# EEG_Preprocessing.net
KiCad netlist of a schematic drawn in Altium Designer
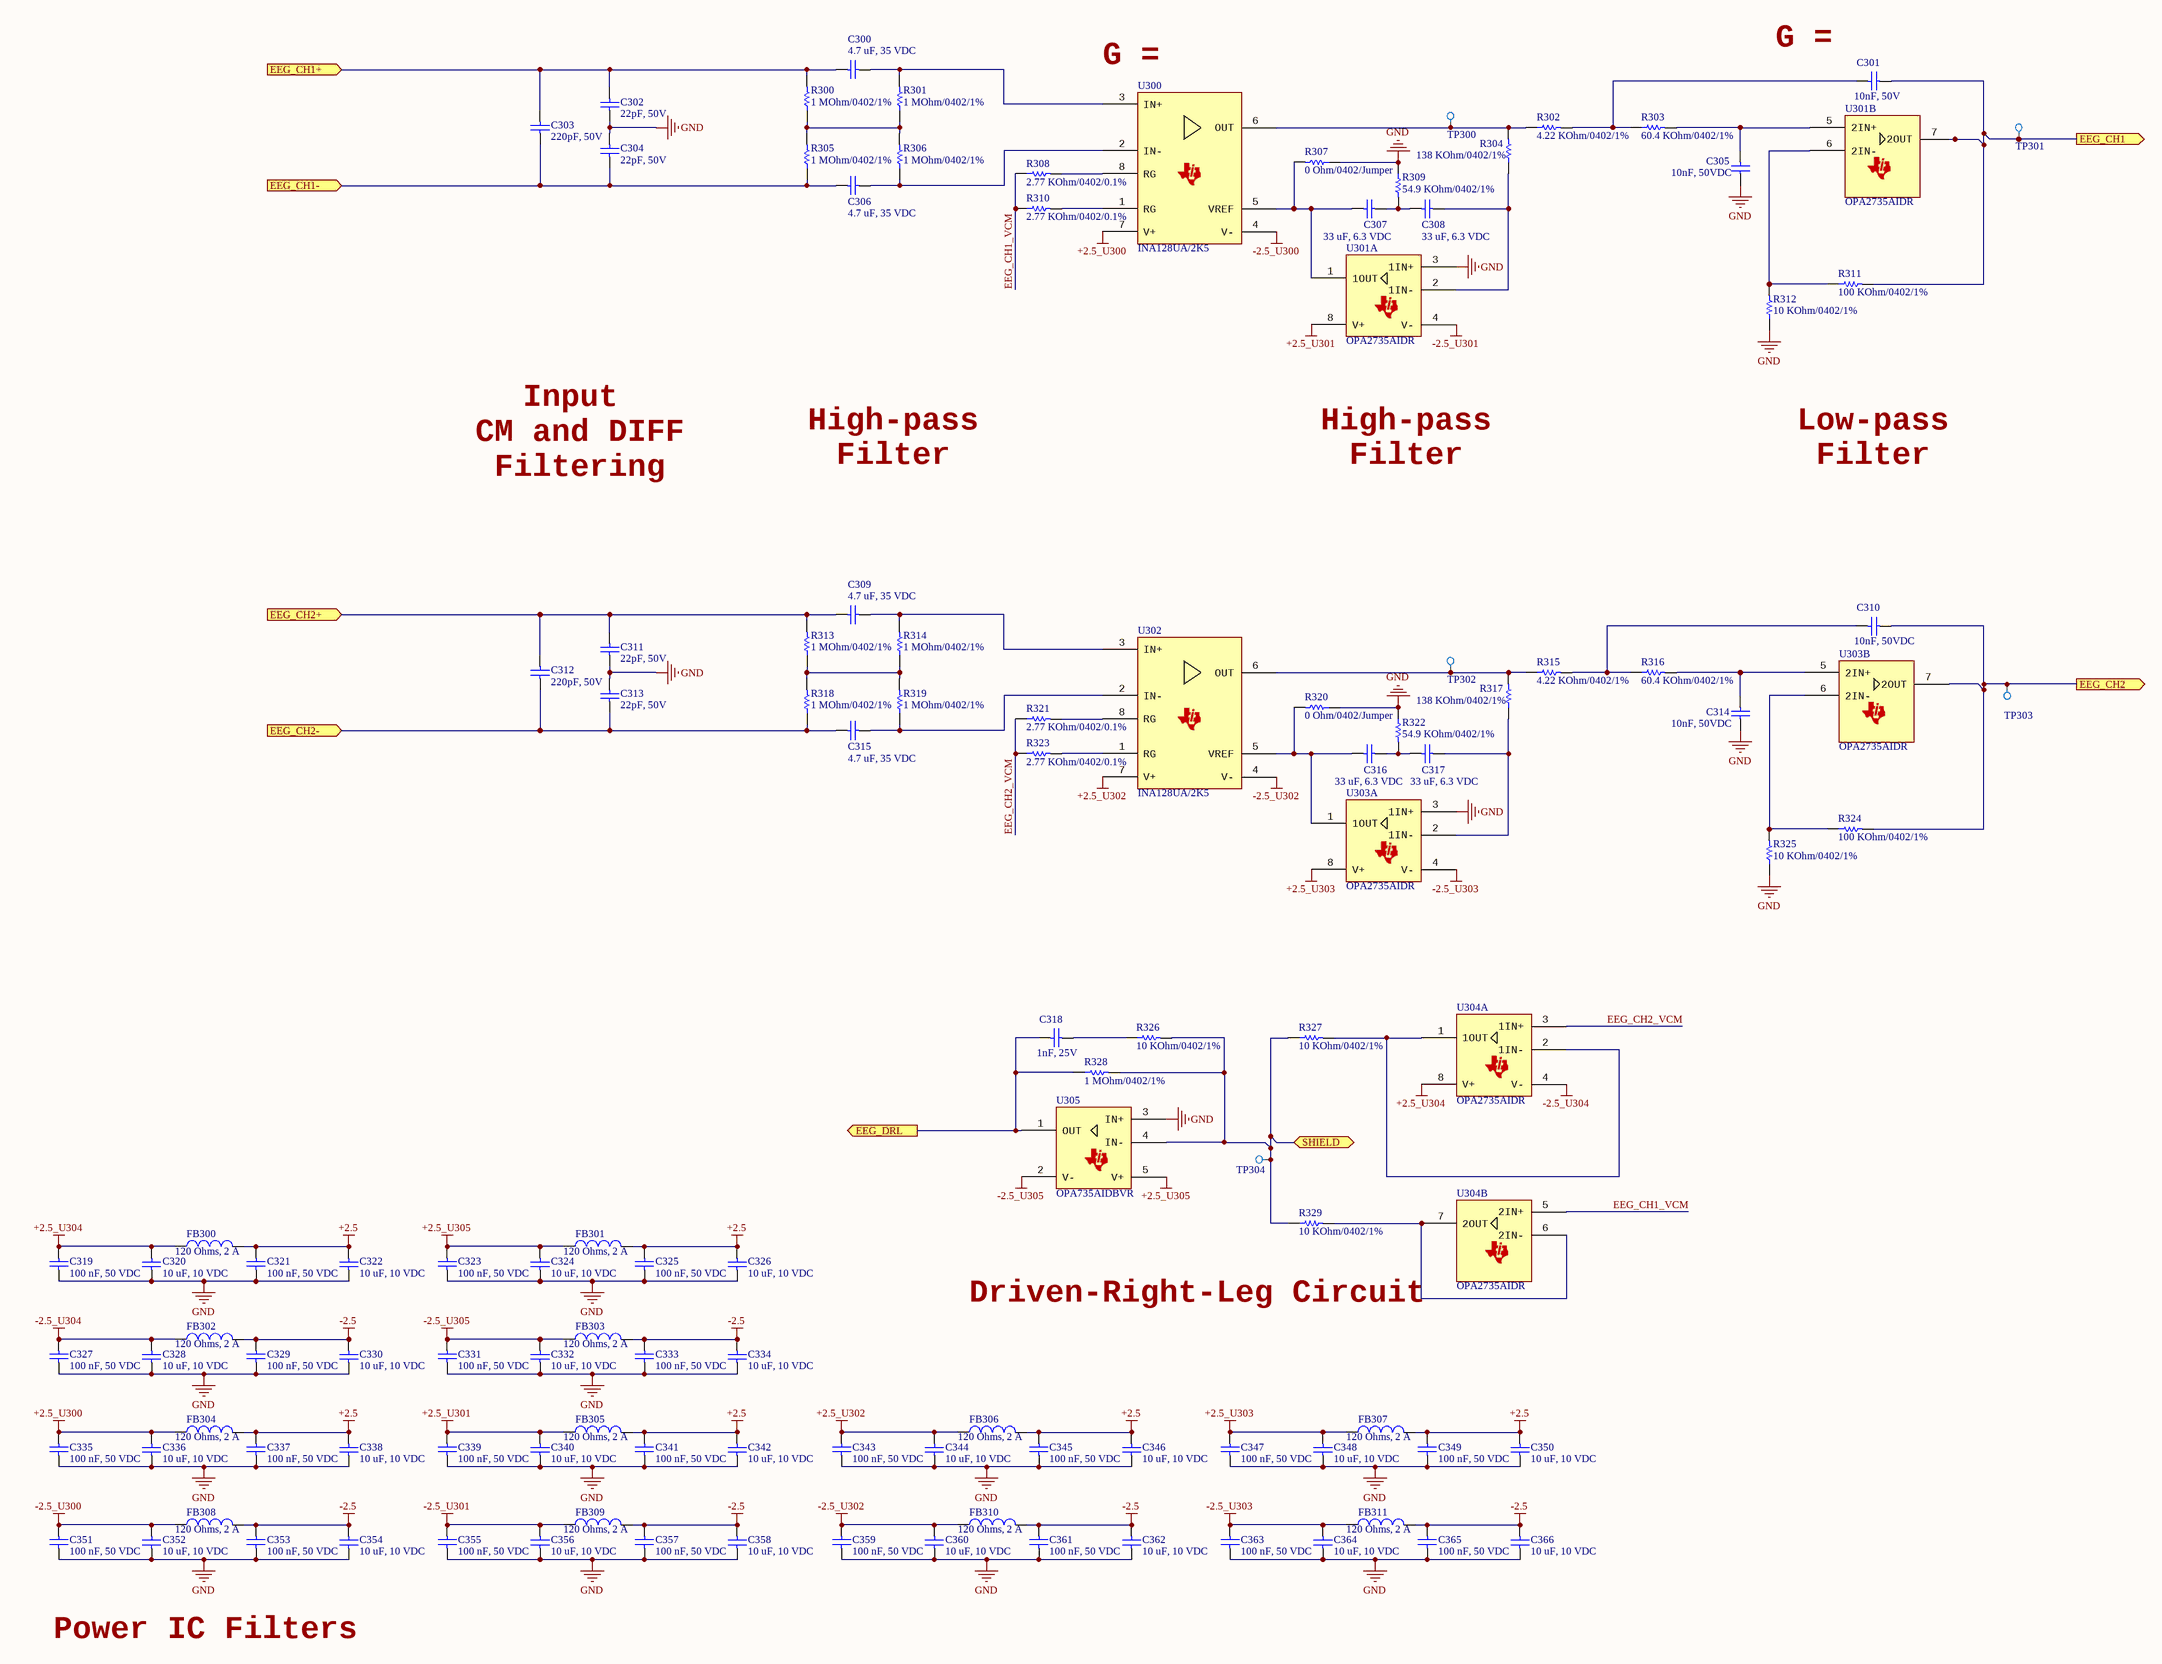
[diagram p0: EEG Preprocessing.SchDoc]

(export (version "E")
  (design (tool "Eeschema 10.0.6"))
  (components
    (comp (ref "C300")
      (value "4.7 uF, 35 VDC")
      (footprint "CAP_0603")
      (description "CAP, size 0603, 4.7 uF, 35 VDC")
      (fields (field (name "TOLERANCE") "+/-10%"))
      (libsource (lib "Altium_Ceramic_Cap") (part "0106034751035"))
    )
    (comp (ref "C301")
      (value "10nF, 50V")
      (footprint "WCAP-CSGP_0402_L1W0.5H0.5")
      (description "WCAP-CSGP Multilayer Ceramic Chip Capacitor, General Purpose, size 0402, X7R, 10nF, 50V")
      (fields
        (field (name "MANUFACTURER PART NUMBER") "885012205067")
        (field (name "MANUFACTURER") "Wurth Elektronik")
      )
      (libsource (lib "Altium_WCAP-CSGP (rev24c)") (part "885012205067"))
    )
    (comp (ref "C302")
      (value "22pF, 50V")
      (footprint "WCAP-CSGP_0402_L1W0.5H0.5")
      (description "WCAP-CSGP Multilayer Ceramic Chip Capacitor, General Purpose, size 0402, NP0, 22pF, 50V")
      (fields
        (field (name "MANUFACTURER PART NUMBER") "885012005057")
        (field (name "MANUFACTURER") "Wurth Elektronik")
      )
      (libsource (lib "Altium_WCAP-CSGP (rev24c)") (part "885012005057"))
    )
    (comp (ref "C303")
      (value "220pF, 50V")
      (footprint "WCAP-CSGP_0402_L1W0.5H0.5")
      (description "WCAP-CSGP Multilayer Ceramic Chip Capacitor, General Purpose, size 0402, NP0, 220pF, 50V")
      (fields
        (field (name "MANUFACTURER PART NUMBER") "885012005063")
        (field (name "MANUFACTURER") "Wurth Elektronik")
      )
      (libsource (lib "Altium_WCAP-CSGP (rev24c)") (part "885012005063"))
    )
    (comp (ref "C304")
      (value "22pF, 50V")
      (footprint "WCAP-CSGP_0402_L1W0.5H0.5")
      (description "WCAP-CSGP Multilayer Ceramic Chip Capacitor, General Purpose, size 0402, NP0, 22pF, 50V")
      (fields
        (field (name "MANUFACTURER PART NUMBER") "885012005057")
        (field (name "MANUFACTURER") "Wurth Elektronik")
      )
      (libsource (lib "Altium_WCAP-CSGP (rev24c)") (part "885012005057"))
    )
    (comp (ref "C305")
      (value "10nF, 50VDC")
      (footprint "WCAP-CSGP_0402_L1W0.5H0.5")
      (description "WCAP-CSGP Multilayer Ceramic Chip Capacitor, General Purpose, size 0402, X7R, 10nF, 50V")
      (fields
        (field (name "MANUFACTURER PART NUMBER") "885012205067")
        (field (name "MANUFACTURER") "Wurth Elektronik")
      )
      (libsource (lib "Altium_WCAP-CSGP (rev24c)") (part "885012205067"))
    )
    (comp (ref "C306")
      (value "4.7 uF, 35 VDC")
      (footprint "CAP_0603")
      (description "CAP, size 0603, 4.7 uF, 35 VDC")
      (fields (field (name "TOLERANCE") "+/-10%"))
      (libsource (lib "Altium_Ceramic_Cap") (part "0106034751035"))
    )
    (comp (ref "C307")
      (value "33 uF, 6.3 VDC")
      (footprint "CAP_0805")
      (description "33 µF ±20% 6.3V Ceramic Capacitor X5R 0805 (2012 Metric)")
      (fields (field (name "TOLERANCE") "+/-10%"))
      (libsource (lib "Altium_Ceramic_Cap") (part "0108051061025"))
    )
    (comp (ref "C308")
      (value "33 uF, 6.3 VDC")
      (footprint "CAP_0805")
      (description "33 µF ±20% 6.3V Ceramic Capacitor X5R 0805 (2012 Metric)")
      (fields (field (name "TOLERANCE") "+/-10%"))
      (libsource (lib "Altium_Ceramic_Cap") (part "0108051061025"))
    )
    (comp (ref "C309")
      (value "4.7 uF, 35 VDC")
      (footprint "CAP_0603")
      (description "CAP, size 0603, 4.7 uF, 35 VDC")
      (fields (field (name "TOLERANCE") "+/-10%"))
      (libsource (lib "Altium_Ceramic_Cap") (part "0106034751035"))
    )
    (comp (ref "C310")
      (value "10nF, 50VDC")
      (footprint "WCAP-CSGP_0402_L1W0.5H0.5")
      (description "WCAP-CSGP Multilayer Ceramic Chip Capacitor, General Purpose, size 0402, X7R, 10nF, 50V")
      (fields
        (field (name "MANUFACTURER PART NUMBER") "885012205067")
        (field (name "MANUFACTURER") "Wurth Elektronik")
      )
      (libsource (lib "Altium_WCAP-CSGP (rev24c)") (part "885012205067"))
    )
    (comp (ref "C311")
      (value "22pF, 50V")
      (footprint "WCAP-CSGP_0402_L1W0.5H0.5")
      (description "WCAP-CSGP Multilayer Ceramic Chip Capacitor, General Purpose, size 0402, NP0, 22pF, 50V")
      (fields
        (field (name "MANUFACTURER PART NUMBER") "885012005057")
        (field (name "MANUFACTURER") "Wurth Elektronik")
      )
      (libsource (lib "Altium_WCAP-CSGP (rev24c)") (part "885012005057"))
    )
    (comp (ref "C312")
      (value "220pF, 50V")
      (footprint "WCAP-CSGP_0402_L1W0.5H0.5")
      (description "WCAP-CSGP Multilayer Ceramic Chip Capacitor, General Purpose, size 0402, NP0, 220pF, 50V")
      (fields
        (field (name "MANUFACTURER PART NUMBER") "885012005063")
        (field (name "MANUFACTURER") "Wurth Elektronik")
      )
      (libsource (lib "Altium_WCAP-CSGP (rev24c)") (part "885012005063"))
    )
    (comp (ref "C313")
      (value "22pF, 50V")
      (footprint "WCAP-CSGP_0402_L1W0.5H0.5")
      (description "WCAP-CSGP Multilayer Ceramic Chip Capacitor, General Purpose, size 0402, NP0, 22pF, 50V")
      (fields
        (field (name "MANUFACTURER PART NUMBER") "885012005057")
        (field (name "MANUFACTURER") "Wurth Elektronik")
      )
      (libsource (lib "Altium_WCAP-CSGP (rev24c)") (part "885012005057"))
    )
    (comp (ref "C314")
      (value "10nF, 50VDC")
      (footprint "WCAP-CSGP_0402_L1W0.5H0.5")
      (description "WCAP-CSGP Multilayer Ceramic Chip Capacitor, General Purpose, size 0402, X7R, 10nF, 50V")
      (fields
        (field (name "MANUFACTURER PART NUMBER") "885012205067")
        (field (name "MANUFACTURER") "Wurth Elektronik")
      )
      (libsource (lib "Altium_WCAP-CSGP (rev24c)") (part "885012205067"))
    )
    (comp (ref "C315")
      (value "4.7 uF, 35 VDC")
      (footprint "CAP_0603")
      (description "CAP, size 0603, 4.7 uF, 35 VDC")
      (fields (field (name "TOLERANCE") "+/-10%"))
      (libsource (lib "Altium_Ceramic_Cap") (part "0106034751035"))
    )
    (comp (ref "C316")
      (value "33 uF, 6.3 VDC")
      (footprint "CAP_0805")
      (description "33 µF ±20% 6.3V Ceramic Capacitor X5R 0805 (2012 Metric)")
      (fields (field (name "TOLERANCE") "+/-10%"))
      (libsource (lib "Altium_Ceramic_Cap") (part "0108051061025"))
    )
    (comp (ref "C317")
      (value "33 uF, 6.3 VDC")
      (footprint "CAP_0805")
      (description "33 µF ±20% 6.3V Ceramic Capacitor X5R 0805 (2012 Metric)")
      (fields (field (name "TOLERANCE") "+/-10%"))
      (libsource (lib "Altium_Ceramic_Cap") (part "0108051061025"))
    )
    (comp (ref "C318")
      (value "1nF, 25V")
      (footprint "WCAP-CSGP_0402_L1W0.5H0.5")
      (description "WCAP-CSGP Multilayer Ceramic Chip Capacitor, General Purpose, size 0402, X7R, 1nF, 25V")
      (fields
        (field (name "MANUFACTURER PART NUMBER") "885012205044")
        (field (name "MANUFACTURER") "Wurth Elektronik")
      )
      (libsource (lib "Altium_WCAP-CSGP (rev24c)") (part "885012205044"))
    )
    (comp (ref "C319")
      (value "100 nF, 50 VDC")
      (footprint "CAP_0603")
      (description "CAP, size 0603, 100 nF, 50 VDC")
      (fields (field (name "TOLERANCE") "+/-10%"))
      (libsource (lib "Altium_Ceramic_Cap") (part "0106031041050"))
    )
    (comp (ref "C320")
      (value "10 uF, 10 VDC")
      (footprint "CAP_0603")
      (description "CAP, size 0603, 10 uF, 10 VDC")
      (fields (field (name "TOLERANCE") "+/-10%"))
      (libsource (lib "Altium_Ceramic_Cap") (part "0106031061010"))
    )
    (comp (ref "C321")
      (value "100 nF, 50 VDC")
      (footprint "CAP_0603")
      (description "CAP, size 0603, 100 nF, 50 VDC")
      (fields (field (name "TOLERANCE") "+/-10%"))
      (libsource (lib "Altium_Ceramic_Cap") (part "0106031041050"))
    )
    (comp (ref "C322")
      (value "10 uF, 10 VDC")
      (footprint "CAP_0603")
      (description "CAP, size 0603, 10 uF, 10 VDC")
      (fields (field (name "TOLERANCE") "+/-10%"))
      (libsource (lib "Altium_Ceramic_Cap") (part "0106031061010"))
    )
    (comp (ref "C323")
      (value "100 nF, 50 VDC")
      (footprint "CAP_0603")
      (description "CAP, size 0603, 100 nF, 50 VDC")
      (fields (field (name "TOLERANCE") "+/-10%"))
      (libsource (lib "Altium_Ceramic_Cap") (part "0106031041050"))
    )
    (comp (ref "C324")
      (value "10 uF, 10 VDC")
      (footprint "CAP_0603")
      (description "CAP, size 0603, 10 uF, 10 VDC")
      (fields (field (name "TOLERANCE") "+/-10%"))
      (libsource (lib "Altium_Ceramic_Cap") (part "0106031061010"))
    )
    (comp (ref "C325")
      (value "100 nF, 50 VDC")
      (footprint "CAP_0603")
      (description "CAP, size 0603, 100 nF, 50 VDC")
      (fields (field (name "TOLERANCE") "+/-10%"))
      (libsource (lib "Altium_Ceramic_Cap") (part "0106031041050"))
    )
    (comp (ref "C326")
      (value "10 uF, 10 VDC")
      (footprint "CAP_0603")
      (description "CAP, size 0603, 10 uF, 10 VDC")
      (fields (field (name "TOLERANCE") "+/-10%"))
      (libsource (lib "Altium_Ceramic_Cap") (part "0106031061010"))
    )
    (comp (ref "C327")
      (value "100 nF, 50 VDC")
      (footprint "CAP_0603")
      (description "CAP, size 0603, 100 nF, 50 VDC")
      (fields (field (name "TOLERANCE") "+/-10%"))
      (libsource (lib "Altium_Ceramic_Cap") (part "0106031041050"))
    )
    (comp (ref "C328")
      (value "10 uF, 10 VDC")
      (footprint "CAP_0603")
      (description "CAP, size 0603, 10 uF, 10 VDC")
      (fields (field (name "TOLERANCE") "+/-10%"))
      (libsource (lib "Altium_Ceramic_Cap") (part "0106031061010"))
    )
    (comp (ref "C329")
      (value "100 nF, 50 VDC")
      (footprint "CAP_0603")
      (description "CAP, size 0603, 100 nF, 50 VDC")
      (fields (field (name "TOLERANCE") "+/-10%"))
      (libsource (lib "Altium_Ceramic_Cap") (part "0106031041050"))
    )
    (comp (ref "C330")
      (value "10 uF, 10 VDC")
      (footprint "CAP_0603")
      (description "CAP, size 0603, 10 uF, 10 VDC")
      (fields (field (name "TOLERANCE") "+/-10%"))
      (libsource (lib "Altium_Ceramic_Cap") (part "0106031061010"))
    )
    (comp (ref "C331")
      (value "100 nF, 50 VDC")
      (footprint "CAP_0603")
      (description "CAP, size 0603, 100 nF, 50 VDC")
      (fields (field (name "TOLERANCE") "+/-10%"))
      (libsource (lib "Altium_Ceramic_Cap") (part "0106031041050"))
    )
    (comp (ref "C332")
      (value "10 uF, 10 VDC")
      (footprint "CAP_0603")
      (description "CAP, size 0603, 10 uF, 10 VDC")
      (fields (field (name "TOLERANCE") "+/-10%"))
      (libsource (lib "Altium_Ceramic_Cap") (part "0106031061010"))
    )
    (comp (ref "C333")
      (value "100 nF, 50 VDC")
      (footprint "CAP_0603")
      (description "CAP, size 0603, 100 nF, 50 VDC")
      (fields (field (name "TOLERANCE") "+/-10%"))
      (libsource (lib "Altium_Ceramic_Cap") (part "0106031041050"))
    )
    (comp (ref "C334")
      (value "10 uF, 10 VDC")
      (footprint "CAP_0603")
      (description "CAP, size 0603, 10 uF, 10 VDC")
      (fields (field (name "TOLERANCE") "+/-10%"))
      (libsource (lib "Altium_Ceramic_Cap") (part "0106031061010"))
    )
    (comp (ref "C335")
      (value "100 nF, 50 VDC")
      (footprint "CAP_0603")
      (description "CAP, size 0603, 100 nF, 50 VDC")
      (fields (field (name "TOLERANCE") "+/-10%"))
      (libsource (lib "Altium_Ceramic_Cap") (part "0106031041050"))
    )
    (comp (ref "C336")
      (value "10 uF, 10 VDC")
      (footprint "CAP_0603")
      (description "CAP, size 0603, 10 uF, 10 VDC")
      (fields (field (name "TOLERANCE") "+/-10%"))
      (libsource (lib "Altium_Ceramic_Cap") (part "0106031061010"))
    )
    (comp (ref "C337")
      (value "100 nF, 50 VDC")
      (footprint "CAP_0603")
      (description "CAP, size 0603, 100 nF, 50 VDC")
      (fields (field (name "TOLERANCE") "+/-10%"))
      (libsource (lib "Altium_Ceramic_Cap") (part "0106031041050"))
    )
    (comp (ref "C338")
      (value "10 uF, 10 VDC")
      (footprint "CAP_0603")
      (description "CAP, size 0603, 10 uF, 10 VDC")
      (fields (field (name "TOLERANCE") "+/-10%"))
      (libsource (lib "Altium_Ceramic_Cap") (part "0106031061010"))
    )
    (comp (ref "C339")
      (value "100 nF, 50 VDC")
      (footprint "CAP_0603")
      (description "CAP, size 0603, 100 nF, 50 VDC")
      (fields (field (name "TOLERANCE") "+/-10%"))
      (libsource (lib "Altium_Ceramic_Cap") (part "0106031041050"))
    )
    (comp (ref "C340")
      (value "10 uF, 10 VDC")
      (footprint "CAP_0603")
      (description "CAP, size 0603, 10 uF, 10 VDC")
      (fields (field (name "TOLERANCE") "+/-10%"))
      (libsource (lib "Altium_Ceramic_Cap") (part "0106031061010"))
    )
    (comp (ref "C341")
      (value "100 nF, 50 VDC")
      (footprint "CAP_0603")
      (description "CAP, size 0603, 100 nF, 50 VDC")
      (fields (field (name "TOLERANCE") "+/-10%"))
      (libsource (lib "Altium_Ceramic_Cap") (part "0106031041050"))
    )
    (comp (ref "C342")
      (value "10 uF, 10 VDC")
      (footprint "CAP_0603")
      (description "CAP, size 0603, 10 uF, 10 VDC")
      (fields (field (name "TOLERANCE") "+/-10%"))
      (libsource (lib "Altium_Ceramic_Cap") (part "0106031061010"))
    )
    (comp (ref "C343")
      (value "100 nF, 50 VDC")
      (footprint "CAP_0603")
      (description "CAP, size 0603, 100 nF, 50 VDC")
      (fields (field (name "TOLERANCE") "+/-10%"))
      (libsource (lib "Altium_Ceramic_Cap") (part "0106031041050"))
    )
    (comp (ref "C344")
      (value "10 uF, 10 VDC")
      (footprint "CAP_0603")
      (description "CAP, size 0603, 10 uF, 10 VDC")
      (fields (field (name "TOLERANCE") "+/-10%"))
      (libsource (lib "Altium_Ceramic_Cap") (part "0106031061010"))
    )
    (comp (ref "C345")
      (value "100 nF, 50 VDC")
      (footprint "CAP_0603")
      (description "CAP, size 0603, 100 nF, 50 VDC")
      (fields (field (name "TOLERANCE") "+/-10%"))
      (libsource (lib "Altium_Ceramic_Cap") (part "0106031041050"))
    )
    (comp (ref "C346")
      (value "10 uF, 10 VDC")
      (footprint "CAP_0603")
      (description "CAP, size 0603, 10 uF, 10 VDC")
      (fields (field (name "TOLERANCE") "+/-10%"))
      (libsource (lib "Altium_Ceramic_Cap") (part "0106031061010"))
    )
    (comp (ref "C347")
      (value "100 nF, 50 VDC")
      (footprint "CAP_0603")
      (description "CAP, size 0603, 100 nF, 50 VDC")
      (fields (field (name "TOLERANCE") "+/-10%"))
      (libsource (lib "Altium_Ceramic_Cap") (part "0106031041050"))
    )
    (comp (ref "C348")
      (value "10 uF, 10 VDC")
      (footprint "CAP_0603")
      (description "CAP, size 0603, 10 uF, 10 VDC")
      (fields (field (name "TOLERANCE") "+/-10%"))
      (libsource (lib "Altium_Ceramic_Cap") (part "0106031061010"))
    )
    (comp (ref "C349")
      (value "100 nF, 50 VDC")
      (footprint "CAP_0603")
      (description "CAP, size 0603, 100 nF, 50 VDC")
      (fields (field (name "TOLERANCE") "+/-10%"))
      (libsource (lib "Altium_Ceramic_Cap") (part "0106031041050"))
    )
    (comp (ref "C350")
      (value "10 uF, 10 VDC")
      (footprint "CAP_0603")
      (description "CAP, size 0603, 10 uF, 10 VDC")
      (fields (field (name "TOLERANCE") "+/-10%"))
      (libsource (lib "Altium_Ceramic_Cap") (part "0106031061010"))
    )
    (comp (ref "C351")
      (value "100 nF, 50 VDC")
      (footprint "CAP_0603")
      (description "CAP, size 0603, 100 nF, 50 VDC")
      (fields (field (name "TOLERANCE") "+/-10%"))
      (libsource (lib "Altium_Ceramic_Cap") (part "0106031041050"))
    )
    (comp (ref "C352")
      (value "10 uF, 10 VDC")
      (footprint "CAP_0603")
      (description "CAP, size 0603, 10 uF, 10 VDC")
      (fields (field (name "TOLERANCE") "+/-10%"))
      (libsource (lib "Altium_Ceramic_Cap") (part "0106031061010"))
    )
    (comp (ref "C353")
      (value "100 nF, 50 VDC")
      (footprint "CAP_0603")
      (description "CAP, size 0603, 100 nF, 50 VDC")
      (fields (field (name "TOLERANCE") "+/-10%"))
      (libsource (lib "Altium_Ceramic_Cap") (part "0106031041050"))
    )
    (comp (ref "C354")
      (value "10 uF, 10 VDC")
      (footprint "CAP_0603")
      (description "CAP, size 0603, 10 uF, 10 VDC")
      (fields (field (name "TOLERANCE") "+/-10%"))
      (libsource (lib "Altium_Ceramic_Cap") (part "0106031061010"))
    )
    (comp (ref "C355")
      (value "100 nF, 50 VDC")
      (footprint "CAP_0603")
      (description "CAP, size 0603, 100 nF, 50 VDC")
      (fields (field (name "TOLERANCE") "+/-10%"))
      (libsource (lib "Altium_Ceramic_Cap") (part "0106031041050"))
    )
    (comp (ref "C356")
      (value "10 uF, 10 VDC")
      (footprint "CAP_0603")
      (description "CAP, size 0603, 10 uF, 10 VDC")
      (fields (field (name "TOLERANCE") "+/-10%"))
      (libsource (lib "Altium_Ceramic_Cap") (part "0106031061010"))
    )
    (comp (ref "C357")
      (value "100 nF, 50 VDC")
      (footprint "CAP_0603")
      (description "CAP, size 0603, 100 nF, 50 VDC")
      (fields (field (name "TOLERANCE") "+/-10%"))
      (libsource (lib "Altium_Ceramic_Cap") (part "0106031041050"))
    )
    (comp (ref "C358")
      (value "10 uF, 10 VDC")
      (footprint "CAP_0603")
      (description "CAP, size 0603, 10 uF, 10 VDC")
      (fields (field (name "TOLERANCE") "+/-10%"))
      (libsource (lib "Altium_Ceramic_Cap") (part "0106031061010"))
    )
    (comp (ref "C359")
      (value "100 nF, 50 VDC")
      (footprint "CAP_0603")
      (description "CAP, size 0603, 100 nF, 50 VDC")
      (fields (field (name "TOLERANCE") "+/-10%"))
      (libsource (lib "Altium_Ceramic_Cap") (part "0106031041050"))
    )
    (comp (ref "C360")
      (value "10 uF, 10 VDC")
      (footprint "CAP_0603")
      (description "CAP, size 0603, 10 uF, 10 VDC")
      (fields (field (name "TOLERANCE") "+/-10%"))
      (libsource (lib "Altium_Ceramic_Cap") (part "0106031061010"))
    )
    (comp (ref "C361")
      (value "100 nF, 50 VDC")
      (footprint "CAP_0603")
      (description "CAP, size 0603, 100 nF, 50 VDC")
      (fields (field (name "TOLERANCE") "+/-10%"))
      (libsource (lib "Altium_Ceramic_Cap") (part "0106031041050"))
    )
    (comp (ref "C362")
      (value "10 uF, 10 VDC")
      (footprint "CAP_0603")
      (description "CAP, size 0603, 10 uF, 10 VDC")
      (fields (field (name "TOLERANCE") "+/-10%"))
      (libsource (lib "Altium_Ceramic_Cap") (part "0106031061010"))
    )
    (comp (ref "C363")
      (value "100 nF, 50 VDC")
      (footprint "CAP_0603")
      (description "CAP, size 0603, 100 nF, 50 VDC")
      (fields (field (name "TOLERANCE") "+/-10%"))
      (libsource (lib "Altium_Ceramic_Cap") (part "0106031041050"))
    )
    (comp (ref "C364")
      (value "10 uF, 10 VDC")
      (footprint "CAP_0603")
      (description "CAP, size 0603, 10 uF, 10 VDC")
      (fields (field (name "TOLERANCE") "+/-10%"))
      (libsource (lib "Altium_Ceramic_Cap") (part "0106031061010"))
    )
    (comp (ref "C365")
      (value "100 nF, 50 VDC")
      (footprint "CAP_0603")
      (description "CAP, size 0603, 100 nF, 50 VDC")
      (fields (field (name "TOLERANCE") "+/-10%"))
      (libsource (lib "Altium_Ceramic_Cap") (part "0106031041050"))
    )
    (comp (ref "C366")
      (value "10 uF, 10 VDC")
      (footprint "CAP_0603")
      (description "CAP, size 0603, 10 uF, 10 VDC")
      (fields (field (name "TOLERANCE") "+/-10%"))
      (libsource (lib "Altium_Ceramic_Cap") (part "0106031061010"))
    )
    (comp (ref "FB300")
      (value "120 Ohms, 2 A")
      (footprint "FER_0603")
      (description "Ferrite, 0603, 120 Ohms, 2 A")
      (fields (field (name "TOLERANCE") "+/-25%"))
      (libsource (lib "Altium_Ferrite_Bead") (part "03060312120225"))
    )
    (comp (ref "FB301")
      (value "120 Ohms, 2 A")
      (footprint "FER_0603")
      (description "Ferrite, 0603, 120 Ohms, 2 A")
      (fields (field (name "TOLERANCE") "+/-25%"))
      (libsource (lib "Altium_Ferrite_Bead") (part "03060312120225"))
    )
    (comp (ref "FB302")
      (value "120 Ohms, 2 A")
      (footprint "FER_0603")
      (description "Ferrite, 0603, 120 Ohms, 2 A")
      (fields (field (name "TOLERANCE") "+/-25%"))
      (libsource (lib "Altium_Ferrite_Bead") (part "03060312120225"))
    )
    (comp (ref "FB303")
      (value "120 Ohms, 2 A")
      (footprint "FER_0603")
      (description "Ferrite, 0603, 120 Ohms, 2 A")
      (fields (field (name "TOLERANCE") "+/-25%"))
      (libsource (lib "Altium_Ferrite_Bead") (part "03060312120225"))
    )
    (comp (ref "FB304")
      (value "120 Ohms, 2 A")
      (footprint "FER_0603")
      (description "Ferrite, 0603, 120 Ohms, 2 A")
      (fields (field (name "TOLERANCE") "+/-25%"))
      (libsource (lib "Altium_Ferrite_Bead") (part "03060312120225"))
    )
    (comp (ref "FB305")
      (value "120 Ohms, 2 A")
      (footprint "FER_0603")
      (description "Ferrite, 0603, 120 Ohms, 2 A")
      (fields (field (name "TOLERANCE") "+/-25%"))
      (libsource (lib "Altium_Ferrite_Bead") (part "03060312120225"))
    )
    (comp (ref "FB306")
      (value "120 Ohms, 2 A")
      (footprint "FER_0603")
      (description "Ferrite, 0603, 120 Ohms, 2 A")
      (fields (field (name "TOLERANCE") "+/-25%"))
      (libsource (lib "Altium_Ferrite_Bead") (part "03060312120225"))
    )
    (comp (ref "FB307")
      (value "120 Ohms, 2 A")
      (footprint "FER_0603")
      (description "Ferrite, 0603, 120 Ohms, 2 A")
      (fields (field (name "TOLERANCE") "+/-25%"))
      (libsource (lib "Altium_Ferrite_Bead") (part "03060312120225"))
    )
    (comp (ref "FB308")
      (value "120 Ohms, 2 A")
      (footprint "FER_0603")
      (description "Ferrite, 0603, 120 Ohms, 2 A")
      (fields (field (name "TOLERANCE") "+/-25%"))
      (libsource (lib "Altium_Ferrite_Bead") (part "03060312120225"))
    )
    (comp (ref "FB309")
      (value "120 Ohms, 2 A")
      (footprint "FER_0603")
      (description "Ferrite, 0603, 120 Ohms, 2 A")
      (fields (field (name "TOLERANCE") "+/-25%"))
      (libsource (lib "Altium_Ferrite_Bead") (part "03060312120225"))
    )
    (comp (ref "FB310")
      (value "120 Ohms, 2 A")
      (footprint "FER_0603")
      (description "Ferrite, 0603, 120 Ohms, 2 A")
      (fields (field (name "TOLERANCE") "+/-25%"))
      (libsource (lib "Altium_Ferrite_Bead") (part "03060312120225"))
    )
    (comp (ref "FB311")
      (value "120 Ohms, 2 A")
      (footprint "FER_0603")
      (description "Ferrite, 0603, 120 Ohms, 2 A")
      (fields (field (name "TOLERANCE") "+/-25%"))
      (libsource (lib "Altium_Ferrite_Bead") (part "03060312120225"))
    )
    (comp (ref "R300")
      (value "1 MOhm/0402/1%")
      (footprint "R0402")
      (description "Code 105, 1/16W 1%")
      (fields (field (name "Comment") "Resistor 1 MOhm 0402 1%"))
      (libsource (lib "Giang_Resistor") (part "Resistor 1 MOhm 0402 1%"))
    )
    (comp (ref "R301")
      (value "1 MOhm/0402/1%")
      (footprint "R0402")
      (description "Code 105, 1/16W 1%")
      (fields (field (name "Comment") "Resistor 1 MOhm 0402 1%"))
      (libsource (lib "Giang_Resistor") (part "Resistor 1 MOhm 0402 1%"))
    )
    (comp (ref "R302")
      (value "4.22 KOhm/0402/1%")
      (footprint "R0402")
      (description "4.22 kOhms ±1% 0.1W, 1/10W Chip Resistor 0402 (1005 Metric) Automotive AEC-Q200 Thick Film")
      (fields (field (name "Comment") "Resistor 4.22 KOhm 0402 1%"))
      (libsource (lib "Giang_Resistor") (part "Resistor 4.22 KOhm 0402 1%"))
    )
    (comp (ref "R303")
      (value "60.4 KOhm/0402/1%")
      (footprint "R0402")
      (description "60.4 kOhms ±1% 0.063W, 1/16W Chip Resistor 0402 (1005 Metric) Moisture Resistant Thick Film")
      (fields (field (name "Comment") "Resistor 60.4 KOhm 0402 1%"))
      (libsource (lib "Giang_Resistor") (part "Resistor 60.4 KOhm 0402 1%"))
    )
    (comp (ref "R304")
      (value "138 KOhm/0402/1%")
      (footprint "R0402")
      (fields (field (name "Comment") "Resistor 138 KOhm 0402 1%"))
      (libsource (lib "Giang_Resistor") (part "Resistor 138 KOhm 0402 1%"))
    )
    (comp (ref "R305")
      (value "1 MOhm/0402/1%")
      (footprint "R0402")
      (description "Code 105, 1/16W 1%")
      (fields (field (name "Comment") "Resistor 1 MOhm 0402 1%"))
      (libsource (lib "Giang_Resistor") (part "Resistor 1 MOhm 0402 1%"))
    )
    (comp (ref "R306")
      (value "1 MOhm/0402/1%")
      (footprint "R0402")
      (description "Code 105, 1/16W 1%")
      (fields (field (name "Comment") "Resistor 1 MOhm 0402 1%"))
      (libsource (lib "Giang_Resistor") (part "Resistor 1 MOhm 0402 1%"))
    )
    (comp (ref "R307")
      (value "0 Ohm/0402/Jumper")
      (footprint "R0402")
      (description "0 Ohms Jumper Chip Resistor 0402 (1005 Metric) Moisture Resistant Thick Film")
      (fields (field (name "Comment") "Resistor 0 Ohm 0402"))
      (libsource (lib "Giang_Resistor") (part "Resistor 0 Ohm 0402"))
    )
    (comp (ref "R308")
      (value "2.77 KOhm/0402/0.1%")
      (footprint "R0402")
      (fields (field (name "Comment") "Resistor 2.77 KOhm 0402 1%"))
      (libsource (lib "Giang_Resistor") (part "Resistor 2.77 KOhm 0402 1%"))
    )
    (comp (ref "R309")
      (value "54.9 KOhm/0402/1%")
      (footprint "R0402")
      (fields (field (name "Comment") "Resistor 54.9 KOhm 0402 1%"))
      (libsource (lib "Giang_Resistor") (part "Resistor 54.9 KOhm 0402 1%"))
    )
    (comp (ref "R310")
      (value "2.77 KOhm/0402/0.1%")
      (footprint "R0402")
      (fields (field (name "Comment") "Resistor 2.77 KOhm 0402 1%"))
      (libsource (lib "Giang_Resistor") (part "Resistor 2.77 KOhm 0402 1%"))
    )
    (comp (ref "R311")
      (value "100 KOhm/0402/1%")
      (footprint "R0402")
      (description "Code 104, 1/16W 1%")
      (fields (field (name "Comment") "Resistor 100 KOhm 0402 1%"))
      (libsource (lib "Giang_Resistor") (part "Resistor 100 KOhm 0402 1%"))
    )
    (comp (ref "R312")
      (value "10 KOhm/0402/1%")
      (footprint "R0402")
      (description "Code 103, 1/16W 1%")
      (fields (field (name "Comment") "Resistor 10 KOhm 0402 1%"))
      (libsource (lib "Giang_Resistor") (part "Resistor 10 KOhm 0402 1%"))
    )
    (comp (ref "R313")
      (value "1 MOhm/0402/1%")
      (footprint "R0402")
      (description "Code 105, 1/16W 1%")
      (fields (field (name "Comment") "Resistor 1 MOhm 0402 1%"))
      (libsource (lib "Giang_Resistor") (part "Resistor 1 MOhm 0402 1%"))
    )
    (comp (ref "R314")
      (value "1 MOhm/0402/1%")
      (footprint "R0402")
      (description "Code 105, 1/16W 1%")
      (fields (field (name "Comment") "Resistor 1 MOhm 0402 1%"))
      (libsource (lib "Giang_Resistor") (part "Resistor 1 MOhm 0402 1%"))
    )
    (comp (ref "R315")
      (value "4.22 KOhm/0402/1%")
      (footprint "R0402")
      (description "4.22 kOhms ±1% 0.1W, 1/10W Chip Resistor 0402 (1005 Metric) Automotive AEC-Q200 Thick Film")
      (fields (field (name "Comment") "Resistor 4.22 KOhm 0402 1%"))
      (libsource (lib "Giang_Resistor") (part "Resistor 4.22 KOhm 0402 1%"))
    )
    (comp (ref "R316")
      (value "60.4 KOhm/0402/1%")
      (footprint "R0402")
      (description "60.4 kOhms ±1% 0.063W, 1/16W Chip Resistor 0402 (1005 Metric) Moisture Resistant Thick Film")
      (fields (field (name "Comment") "Resistor 60.4 KOhm 0402 1%"))
      (libsource (lib "Giang_Resistor") (part "Resistor 60.4 KOhm 0402 1%"))
    )
    (comp (ref "R317")
      (value "138 KOhm/0402/1%")
      (footprint "R0402")
      (fields (field (name "Comment") "Resistor 138 KOhm 0402 1%"))
      (libsource (lib "Giang_Resistor") (part "Resistor 138 KOhm 0402 1%"))
    )
    (comp (ref "R318")
      (value "1 MOhm/0402/1%")
      (footprint "R0402")
      (description "Code 105, 1/16W 1%")
      (fields (field (name "Comment") "Resistor 1 MOhm 0402 1%"))
      (libsource (lib "Giang_Resistor") (part "Resistor 1 MOhm 0402 1%"))
    )
    (comp (ref "R319")
      (value "1 MOhm/0402/1%")
      (footprint "R0402")
      (description "Code 105, 1/16W 1%")
      (fields (field (name "Comment") "Resistor 1 MOhm 0402 1%"))
      (libsource (lib "Giang_Resistor") (part "Resistor 1 MOhm 0402 1%"))
    )
    (comp (ref "R320")
      (value "0 Ohm/0402/Jumper")
      (footprint "R0402")
      (description "0 Ohms Jumper Chip Resistor 0402 (1005 Metric) Moisture Resistant Thick Film")
      (fields (field (name "Comment") "Resistor 0 Ohm 0402"))
      (libsource (lib "Giang_Resistor") (part "Resistor 0 Ohm 0402"))
    )
    (comp (ref "R321")
      (value "2.77 KOhm/0402/0.1%")
      (footprint "R0402")
      (fields (field (name "Comment") "Resistor 2.77 KOhm 0402 1%"))
      (libsource (lib "Giang_Resistor") (part "Resistor 2.77 KOhm 0402 1%"))
    )
    (comp (ref "R322")
      (value "54.9 KOhm/0402/1%")
      (footprint "R0402")
      (fields (field (name "Comment") "Resistor 54.9 KOhm 0402 1%"))
      (libsource (lib "Giang_Resistor") (part "Resistor 54.9 KOhm 0402 1%"))
    )
    (comp (ref "R323")
      (value "2.77 KOhm/0402/0.1%")
      (footprint "R0402")
      (fields (field (name "Comment") "Resistor 2.77 KOhm 0402 1%"))
      (libsource (lib "Giang_Resistor") (part "Resistor 2.77 KOhm 0402 1%"))
    )
    (comp (ref "R324")
      (value "100 KOhm/0402/1%")
      (footprint "R0402")
      (description "Code 104, 1/16W 1%")
      (fields (field (name "Comment") "Resistor 100 KOhm 0402 1%"))
      (libsource (lib "Giang_Resistor") (part "Resistor 100 KOhm 0402 1%"))
    )
    (comp (ref "R325")
      (value "10 KOhm/0402/1%")
      (footprint "R0402")
      (description "Code 103, 1/16W 1%")
      (fields (field (name "Comment") "Resistor 10 KOhm 0402 1%"))
      (libsource (lib "Giang_Resistor") (part "Resistor 10 KOhm 0402 1%"))
    )
    (comp (ref "R326")
      (value "10 KOhm/0402/1%")
      (footprint "R0402")
      (description "Code 103, 1/16W 1%")
      (fields (field (name "Comment") "Resistor 10 KOhm 0402 1%"))
      (libsource (lib "Giang_Resistor") (part "Resistor 10 KOhm 0402 1%"))
    )
    (comp (ref "R327")
      (value "10 KOhm/0402/1%")
      (footprint "R0402")
      (description "Code 103, 1/16W 1%")
      (fields (field (name "Comment") "Resistor 10 KOhm 0402 1%"))
      (libsource (lib "Giang_Resistor") (part "Resistor 10 KOhm 0402 1%"))
    )
    (comp (ref "R328")
      (value "1 MOhm/0402/1%")
      (footprint "R0402")
      (description "Code 105, 1/16W 1%")
      (fields (field (name "Comment") "Resistor 1 MOhm 0402 1%"))
      (libsource (lib "Giang_Resistor") (part "Resistor 1 MOhm 0402 1%"))
    )
    (comp (ref "R329")
      (value "10 KOhm/0402/1%")
      (footprint "R0402")
      (description "Code 103, 1/16W 1%")
      (fields (field (name "Comment") "Resistor 10 KOhm 0402 1%"))
      (libsource (lib "Giang_Resistor") (part "Resistor 10 KOhm 0402 1%"))
    )
    (comp (ref "TP300")
      (value "Testpoint_TH")
      (footprint "TestPoint_THTPad_D1.5mm_Drill0.7mm")
      (description "Test Point TEST-1BK")
      (libsource (lib "BluetoothTracking") (part "Testpoint_TH"))
    )
    (comp (ref "TP301")
      (value "Testpoint_TH")
      (footprint "TestPoint_THTPad_D1.5mm_Drill0.7mm")
      (description "Test Point TEST-1BK")
      (libsource (lib "BluetoothTracking") (part "Testpoint_TH"))
    )
    (comp (ref "TP302")
      (value "Testpoint_TH")
      (footprint "TestPoint_THTPad_D1.5mm_Drill0.7mm")
      (description "Test Point TEST-1BK")
      (libsource (lib "BluetoothTracking") (part "Testpoint_TH"))
    )
    (comp (ref "TP303")
      (value "Testpoint_TH")
      (footprint "TestPoint_THTPad_D1.5mm_Drill0.7mm")
      (description "Test Point TEST-1BK")
      (libsource (lib "BluetoothTracking") (part "Testpoint_TH"))
    )
    (comp (ref "TP304")
      (value "Testpoint_TH")
      (footprint "TestPoint_THTPad_D1.5mm_Drill0.7mm")
      (description "Test Point TEST-1BK")
      (libsource (lib "BluetoothTracking") (part "Testpoint_TH"))
    )
    (comp (ref "U300")
      (value "INA128UA/2K5")
      (footprint "SOIC-8")
      (description "Precision, Low Power Instrumentation Amplifiers")
      (libsource (lib "Giang_Amplifiers") (part "INA128UA/2K5"))
    )
    (comp (ref "U301")
      (value "OPA2735AIDR")
      (footprint "SOIC-8")
      (description "0.05μV/°C max, Single-Supply CMOS Operational Amplifiers Zero-drift Series")
      (libsource (lib "Giang_Amplifiers") (part "OPA2735AIDR"))
    )
    (comp (ref "U302")
      (value "INA128UA/2K5")
      (footprint "SOIC-8")
      (description "Precision, Low Power Instrumentation Amplifiers")
      (libsource (lib "Giang_Amplifiers") (part "INA128UA/2K5"))
    )
    (comp (ref "U303")
      (value "OPA2735AIDR")
      (footprint "SOIC-8")
      (description "0.05μV/°C max, Single-Supply CMOS Operational Amplifiers Zero-drift Series")
      (libsource (lib "Giang_Amplifiers") (part "OPA2735AIDR"))
    )
    (comp (ref "U304")
      (value "OPA2735AIDR")
      (footprint "SOIC-8")
      (description "0.05μV/°C max, Single-Supply CMOS Operational Amplifiers Zero-drift Series")
      (libsource (lib "") (part "OPA2735AIDR_1"))
    )
    (comp (ref "U305")
      (value "OPA735AIDBVR")
      (footprint "SOT-23")
      (description "Zero-Drift Amplifier 1 Circuit Rail-to-Rail SOT-23-5")
      (libsource (lib "Giang_Amplifiers") (part "OPA735AIDBVR"))
    )
  )
  (nets
    (net (code "1") (name "+2.5") (class "Default")
      (node (ref "C321") (pin "1") (pinfunction "1_1") (pintype "passive"))
      (node (ref "C322") (pin "2") (pinfunction "2_2") (pintype "passive"))
      (node (ref "C325") (pin "1") (pinfunction "1_1") (pintype "passive"))
      (node (ref "C326") (pin "2") (pinfunction "2_2") (pintype "passive"))
      (node (ref "C337") (pin "1") (pinfunction "1_1") (pintype "passive"))
      (node (ref "C338") (pin "2") (pinfunction "2_2") (pintype "passive"))
      (node (ref "C341") (pin "1") (pinfunction "1_1") (pintype "passive"))
      (node (ref "C342") (pin "2") (pinfunction "2_2") (pintype "passive"))
      (node (ref "C345") (pin "1") (pinfunction "1_1") (pintype "passive"))
      (node (ref "C346") (pin "2") (pinfunction "2_2") (pintype "passive"))
      (node (ref "C349") (pin "1") (pinfunction "1_1") (pintype "passive"))
      (node (ref "C350") (pin "2") (pinfunction "2_2") (pintype "passive"))
      (node (ref "FB300") (pin "2") (pinfunction "2_2") (pintype "passive"))
      (node (ref "FB301") (pin "2") (pinfunction "2_2") (pintype "passive"))
      (node (ref "FB304") (pin "2") (pinfunction "2_2") (pintype "passive"))
      (node (ref "FB305") (pin "2") (pinfunction "2_2") (pintype "passive"))
      (node (ref "FB306") (pin "2") (pinfunction "2_2") (pintype "passive"))
      (node (ref "FB307") (pin "2") (pinfunction "2_2") (pintype "passive"))
    )
    (net (code "2") (name "+2.5_U300") (class "Default")
      (node (ref "C335") (pin "1") (pinfunction "1_1") (pintype "passive"))
      (node (ref "C336") (pin "2") (pinfunction "2_2") (pintype "passive"))
      (node (ref "FB304") (pin "1") (pinfunction "1_1") (pintype "passive"))
      (node (ref "U300") (pin "7") (pinfunction "V+_7") (pintype "passive"))
    )
    (net (code "3") (name "+2.5_U301") (class "Default")
      (node (ref "C339") (pin "1") (pinfunction "1_1") (pintype "passive"))
      (node (ref "C340") (pin "2") (pinfunction "2_2") (pintype "passive"))
      (node (ref "FB305") (pin "1") (pinfunction "1_1") (pintype "passive"))
      (node (ref "U301") (pin "8") (pinfunction "V+_8") (pintype "passive"))
    )
    (net (code "4") (name "+2.5_U302") (class "Default")
      (node (ref "C343") (pin "1") (pinfunction "1_1") (pintype "passive"))
      (node (ref "C344") (pin "2") (pinfunction "2_2") (pintype "passive"))
      (node (ref "FB306") (pin "1") (pinfunction "1_1") (pintype "passive"))
      (node (ref "U302") (pin "7") (pinfunction "V+_7") (pintype "passive"))
    )
    (net (code "5") (name "+2.5_U303") (class "Default")
      (node (ref "C347") (pin "1") (pinfunction "1_1") (pintype "passive"))
      (node (ref "C348") (pin "2") (pinfunction "2_2") (pintype "passive"))
      (node (ref "FB307") (pin "1") (pinfunction "1_1") (pintype "passive"))
      (node (ref "U303") (pin "8") (pinfunction "V+_8") (pintype "passive"))
    )
    (net (code "6") (name "+2.5_U304") (class "Default")
      (node (ref "C319") (pin "1") (pinfunction "1_1") (pintype "passive"))
      (node (ref "C320") (pin "2") (pinfunction "2_2") (pintype "passive"))
      (node (ref "FB300") (pin "1") (pinfunction "1_1") (pintype "passive"))
      (node (ref "U304") (pin "8") (pinfunction "V+_8") (pintype "passive"))
    )
    (net (code "7") (name "+2.5_U305") (class "Default")
      (node (ref "C323") (pin "1") (pinfunction "1_1") (pintype "passive"))
      (node (ref "C324") (pin "2") (pinfunction "2_2") (pintype "passive"))
      (node (ref "FB301") (pin "1") (pinfunction "1_1") (pintype "passive"))
      (node (ref "U305") (pin "5") (pinfunction "V+_5") (pintype "passive"))
    )
    (net (code "8") (name "-2.5") (class "Default")
      (node (ref "C329") (pin "1") (pinfunction "1_1") (pintype "passive"))
      (node (ref "C330") (pin "2") (pinfunction "2_2") (pintype "passive"))
      (node (ref "C333") (pin "1") (pinfunction "1_1") (pintype "passive"))
      (node (ref "C334") (pin "2") (pinfunction "2_2") (pintype "passive"))
      (node (ref "C353") (pin "1") (pinfunction "1_1") (pintype "passive"))
      (node (ref "C354") (pin "2") (pinfunction "2_2") (pintype "passive"))
      (node (ref "C357") (pin "1") (pinfunction "1_1") (pintype "passive"))
      (node (ref "C358") (pin "2") (pinfunction "2_2") (pintype "passive"))
      (node (ref "C361") (pin "1") (pinfunction "1_1") (pintype "passive"))
      (node (ref "C362") (pin "2") (pinfunction "2_2") (pintype "passive"))
      (node (ref "C365") (pin "1") (pinfunction "1_1") (pintype "passive"))
      (node (ref "C366") (pin "2") (pinfunction "2_2") (pintype "passive"))
      (node (ref "FB302") (pin "2") (pinfunction "2_2") (pintype "passive"))
      (node (ref "FB303") (pin "2") (pinfunction "2_2") (pintype "passive"))
      (node (ref "FB308") (pin "2") (pinfunction "2_2") (pintype "passive"))
      (node (ref "FB309") (pin "2") (pinfunction "2_2") (pintype "passive"))
      (node (ref "FB310") (pin "2") (pinfunction "2_2") (pintype "passive"))
      (node (ref "FB311") (pin "2") (pinfunction "2_2") (pintype "passive"))
    )
    (net (code "9") (name "-2.5_U300") (class "Default")
      (node (ref "C351") (pin "1") (pinfunction "1_1") (pintype "passive"))
      (node (ref "C352") (pin "2") (pinfunction "2_2") (pintype "passive"))
      (node (ref "FB308") (pin "1") (pinfunction "1_1") (pintype "passive"))
      (node (ref "U300") (pin "4") (pinfunction "V-_4") (pintype "passive"))
    )
    (net (code "10") (name "-2.5_U301") (class "Default")
      (node (ref "C355") (pin "1") (pinfunction "1_1") (pintype "passive"))
      (node (ref "C356") (pin "2") (pinfunction "2_2") (pintype "passive"))
      (node (ref "FB309") (pin "1") (pinfunction "1_1") (pintype "passive"))
      (node (ref "U301") (pin "4") (pinfunction "V-_4") (pintype "passive"))
    )
    (net (code "11") (name "-2.5_U302") (class "Default")
      (node (ref "C359") (pin "1") (pinfunction "1_1") (pintype "passive"))
      (node (ref "C360") (pin "2") (pinfunction "2_2") (pintype "passive"))
      (node (ref "FB310") (pin "1") (pinfunction "1_1") (pintype "passive"))
      (node (ref "U302") (pin "4") (pinfunction "V-_4") (pintype "passive"))
    )
    (net (code "12") (name "-2.5_U303") (class "Default")
      (node (ref "C363") (pin "1") (pinfunction "1_1") (pintype "passive"))
      (node (ref "C364") (pin "2") (pinfunction "2_2") (pintype "passive"))
      (node (ref "FB311") (pin "1") (pinfunction "1_1") (pintype "passive"))
      (node (ref "U303") (pin "4") (pinfunction "V-_4") (pintype "passive"))
    )
    (net (code "13") (name "-2.5_U304") (class "Default")
      (node (ref "C327") (pin "1") (pinfunction "1_1") (pintype "passive"))
      (node (ref "C328") (pin "2") (pinfunction "2_2") (pintype "passive"))
      (node (ref "FB302") (pin "1") (pinfunction "1_1") (pintype "passive"))
      (node (ref "U304") (pin "4") (pinfunction "V-_4") (pintype "passive"))
    )
    (net (code "14") (name "-2.5_U305") (class "Default")
      (node (ref "C331") (pin "1") (pinfunction "1_1") (pintype "passive"))
      (node (ref "C332") (pin "2") (pinfunction "2_2") (pintype "passive"))
      (node (ref "FB303") (pin "1") (pinfunction "1_1") (pintype "passive"))
      (node (ref "U305") (pin "2") (pinfunction "V-_2") (pintype "passive"))
    )
    (net (code "15") (name "/EEG_CH1") (class "Default")
      (node (ref "C301") (pin "2") (pinfunction "2_2") (pintype "passive"))
      (node (ref "R311") (pin "2") (pinfunction "2_2") (pintype "passive"))
      (node (ref "TP301") (pin "1") (pinfunction "1_1") (pintype "passive"))
      (node (ref "U301") (pin "7") (pinfunction "2OUT_7") (pintype "passive"))
    )
    (net (code "16") (name "/EEG_CH1+") (class "Default")
      (node (ref "C300") (pin "2") (pinfunction "2_2") (pintype "passive"))
      (node (ref "C302") (pin "2") (pinfunction "2_2") (pintype "passive"))
      (node (ref "C303") (pin "2") (pinfunction "2_2") (pintype "passive"))
      (node (ref "R300") (pin "2") (pinfunction "2_2") (pintype "passive"))
    )
    (net (code "17") (name "/EEG_CH1-") (class "Default")
      (node (ref "C303") (pin "1") (pinfunction "1_1") (pintype "passive"))
      (node (ref "C304") (pin "1") (pinfunction "1_1") (pintype "passive"))
      (node (ref "C306") (pin "2") (pinfunction "2_2") (pintype "passive"))
      (node (ref "R305") (pin "1") (pinfunction "1_1") (pintype "passive"))
    )
    (net (code "18") (name "/EEG_CH1_VCM") (class "Default")
      (node (ref "R308") (pin "1") (pinfunction "1_1") (pintype "passive"))
      (node (ref "R310") (pin "1") (pinfunction "1_1") (pintype "passive"))
      (node (ref "U304") (pin "5") (pinfunction "2IN+_5") (pintype "passive"))
    )
    (net (code "19") (name "/EEG_CH2") (class "Default")
      (node (ref "C310") (pin "2") (pinfunction "2_2") (pintype "passive"))
      (node (ref "R324") (pin "2") (pinfunction "2_2") (pintype "passive"))
      (node (ref "TP303") (pin "1") (pinfunction "1_1") (pintype "passive"))
      (node (ref "U303") (pin "7") (pinfunction "2OUT_7") (pintype "passive"))
    )
    (net (code "20") (name "/EEG_CH2+") (class "Default")
      (node (ref "C309") (pin "2") (pinfunction "2_2") (pintype "passive"))
      (node (ref "C311") (pin "2") (pinfunction "2_2") (pintype "passive"))
      (node (ref "C312") (pin "2") (pinfunction "2_2") (pintype "passive"))
      (node (ref "R313") (pin "2") (pinfunction "2_2") (pintype "passive"))
    )
    (net (code "21") (name "/EEG_CH2-") (class "Default")
      (node (ref "C312") (pin "1") (pinfunction "1_1") (pintype "passive"))
      (node (ref "C313") (pin "1") (pinfunction "1_1") (pintype "passive"))
      (node (ref "C315") (pin "2") (pinfunction "2_2") (pintype "passive"))
      (node (ref "R318") (pin "1") (pinfunction "1_1") (pintype "passive"))
    )
    (net (code "22") (name "/EEG_CH2_VCM") (class "Default")
      (node (ref "R321") (pin "1") (pinfunction "1_1") (pintype "passive"))
      (node (ref "R323") (pin "1") (pinfunction "1_1") (pintype "passive"))
      (node (ref "U304") (pin "3") (pinfunction "1IN+_3") (pintype "passive"))
    )
    (net (code "23") (name "/EEG_DRL") (class "Default")
      (node (ref "C318") (pin "1") (pinfunction "1_1") (pintype "passive"))
      (node (ref "R328") (pin "1") (pinfunction "1_1") (pintype "passive"))
      (node (ref "U305") (pin "1") (pinfunction "OUT_1") (pintype "passive"))
    )
    (net (code "24") (name "/SHIELD") (class "Default")
      (node (ref "R326") (pin "2") (pinfunction "2_2") (pintype "passive"))
      (node (ref "R327") (pin "1") (pinfunction "1_1") (pintype "passive"))
      (node (ref "R328") (pin "2") (pinfunction "2_2") (pintype "passive"))
      (node (ref "R329") (pin "1") (pinfunction "1_1") (pintype "passive"))
      (node (ref "TP304") (pin "1") (pinfunction "1_1") (pintype "passive"))
      (node (ref "U305") (pin "4") (pinfunction "IN-_4") (pintype "passive"))
    )
    (net (code "25") (name "GND") (class "Default")
      (node (ref "C302") (pin "1") (pinfunction "1_1") (pintype "passive"))
      (node (ref "C304") (pin "2") (pinfunction "2_2") (pintype "passive"))
      (node (ref "C305") (pin "1") (pinfunction "1_1") (pintype "passive"))
      (node (ref "C311") (pin "1") (pinfunction "1_1") (pintype "passive"))
      (node (ref "C313") (pin "2") (pinfunction "2_2") (pintype "passive"))
      (node (ref "C314") (pin "1") (pinfunction "1_1") (pintype "passive"))
      (node (ref "C319") (pin "2") (pinfunction "2_2") (pintype "passive"))
      (node (ref "C320") (pin "1") (pinfunction "1_1") (pintype "passive"))
      (node (ref "C321") (pin "2") (pinfunction "2_2") (pintype "passive"))
      (node (ref "C322") (pin "1") (pinfunction "1_1") (pintype "passive"))
      (node (ref "C323") (pin "2") (pinfunction "2_2") (pintype "passive"))
      (node (ref "C324") (pin "1") (pinfunction "1_1") (pintype "passive"))
      (node (ref "C325") (pin "2") (pinfunction "2_2") (pintype "passive"))
      (node (ref "C326") (pin "1") (pinfunction "1_1") (pintype "passive"))
      (node (ref "C327") (pin "2") (pinfunction "2_2") (pintype "passive"))
      (node (ref "C328") (pin "1") (pinfunction "1_1") (pintype "passive"))
      (node (ref "C329") (pin "2") (pinfunction "2_2") (pintype "passive"))
      (node (ref "C330") (pin "1") (pinfunction "1_1") (pintype "passive"))
      (node (ref "C331") (pin "2") (pinfunction "2_2") (pintype "passive"))
      (node (ref "C332") (pin "1") (pinfunction "1_1") (pintype "passive"))
      (node (ref "C333") (pin "2") (pinfunction "2_2") (pintype "passive"))
      (node (ref "C334") (pin "1") (pinfunction "1_1") (pintype "passive"))
      (node (ref "C335") (pin "2") (pinfunction "2_2") (pintype "passive"))
      (node (ref "C336") (pin "1") (pinfunction "1_1") (pintype "passive"))
      (node (ref "C337") (pin "2") (pinfunction "2_2") (pintype "passive"))
      (node (ref "C338") (pin "1") (pinfunction "1_1") (pintype "passive"))
      (node (ref "C339") (pin "2") (pinfunction "2_2") (pintype "passive"))
      (node (ref "C340") (pin "1") (pinfunction "1_1") (pintype "passive"))
      (node (ref "C341") (pin "2") (pinfunction "2_2") (pintype "passive"))
      (node (ref "C342") (pin "1") (pinfunction "1_1") (pintype "passive"))
      (node (ref "C343") (pin "2") (pinfunction "2_2") (pintype "passive"))
      (node (ref "C344") (pin "1") (pinfunction "1_1") (pintype "passive"))
      (node (ref "C345") (pin "2") (pinfunction "2_2") (pintype "passive"))
      (node (ref "C346") (pin "1") (pinfunction "1_1") (pintype "passive"))
      (node (ref "C347") (pin "2") (pinfunction "2_2") (pintype "passive"))
      (node (ref "C348") (pin "1") (pinfunction "1_1") (pintype "passive"))
      (node (ref "C349") (pin "2") (pinfunction "2_2") (pintype "passive"))
      (node (ref "C350") (pin "1") (pinfunction "1_1") (pintype "passive"))
      (node (ref "C351") (pin "2") (pinfunction "2_2") (pintype "passive"))
      (node (ref "C352") (pin "1") (pinfunction "1_1") (pintype "passive"))
      (node (ref "C353") (pin "2") (pinfunction "2_2") (pintype "passive"))
      (node (ref "C354") (pin "1") (pinfunction "1_1") (pintype "passive"))
      (node (ref "C355") (pin "2") (pinfunction "2_2") (pintype "passive"))
      (node (ref "C356") (pin "1") (pinfunction "1_1") (pintype "passive"))
      (node (ref "C357") (pin "2") (pinfunction "2_2") (pintype "passive"))
      (node (ref "C358") (pin "1") (pinfunction "1_1") (pintype "passive"))
      (node (ref "C359") (pin "2") (pinfunction "2_2") (pintype "passive"))
      (node (ref "C360") (pin "1") (pinfunction "1_1") (pintype "passive"))
      (node (ref "C361") (pin "2") (pinfunction "2_2") (pintype "passive"))
      (node (ref "C362") (pin "1") (pinfunction "1_1") (pintype "passive"))
      (node (ref "C363") (pin "2") (pinfunction "2_2") (pintype "passive"))
      (node (ref "C364") (pin "1") (pinfunction "1_1") (pintype "passive"))
      (node (ref "C365") (pin "2") (pinfunction "2_2") (pintype "passive"))
      (node (ref "C366") (pin "1") (pinfunction "1_1") (pintype "passive"))
      (node (ref "R307") (pin "1") (pinfunction "1_1") (pintype "passive"))
      (node (ref "R309") (pin "1") (pinfunction "1_1") (pintype "passive"))
      (node (ref "R312") (pin "1") (pinfunction "1_1") (pintype "passive"))
      (node (ref "R320") (pin "1") (pinfunction "1_1") (pintype "passive"))
      (node (ref "R322") (pin "1") (pinfunction "1_1") (pintype "passive"))
      (node (ref "R325") (pin "1") (pinfunction "1_1") (pintype "passive"))
      (node (ref "U301") (pin "3") (pinfunction "1IN+_3") (pintype "passive"))
      (node (ref "U303") (pin "3") (pinfunction "1IN+_3") (pintype "passive"))
      (node (ref "U305") (pin "3") (pinfunction "IN+_3") (pintype "passive"))
    )
    (net (code "26") (name "Net-(C301-Pad1)") (class "Default")
      (node (ref "C301") (pin "1") (pinfunction "1_1") (pintype "passive"))
      (node (ref "R302") (pin "2") (pinfunction "2_2") (pintype "passive"))
      (node (ref "R303") (pin "1") (pinfunction "1_1") (pintype "passive"))
    )
    (net (code "27") (name "Net-(C307-Pad2)") (class "Default")
      (node (ref "C307") (pin "2") (pinfunction "2_2") (pintype "passive"))
      (node (ref "C308") (pin "1") (pinfunction "1_1") (pintype "passive"))
      (node (ref "R309") (pin "2") (pinfunction "2_2") (pintype "passive"))
    )
    (net (code "28") (name "Net-(C310-Pad1)") (class "Default")
      (node (ref "C310") (pin "1") (pinfunction "1_1") (pintype "passive"))
      (node (ref "R315") (pin "2") (pinfunction "2_2") (pintype "passive"))
      (node (ref "R316") (pin "1") (pinfunction "1_1") (pintype "passive"))
    )
    (net (code "29") (name "Net-(C316-Pad2)") (class "Default")
      (node (ref "C316") (pin "2") (pinfunction "2_2") (pintype "passive"))
      (node (ref "C317") (pin "1") (pinfunction "1_1") (pintype "passive"))
      (node (ref "R322") (pin "2") (pinfunction "2_2") (pintype "passive"))
    )
    (net (code "30") (name "Net-(C318-Pad2)") (class "Default")
      (node (ref "C318") (pin "2") (pinfunction "2_2") (pintype "passive"))
      (node (ref "R326") (pin "1") (pinfunction "1_1") (pintype "passive"))
    )
    (net (code "31") (name "Net-(R300-Pad1)") (class "Default")
      (node (ref "R300") (pin "1") (pinfunction "1_1") (pintype "passive"))
      (node (ref "R301") (pin "1") (pinfunction "1_1") (pintype "passive"))
      (node (ref "R305") (pin "2") (pinfunction "2_2") (pintype "passive"))
      (node (ref "R306") (pin "2") (pinfunction "2_2") (pintype "passive"))
    )
    (net (code "32") (name "Net-(R308-Pad2)") (class "Default")
      (node (ref "R308") (pin "2") (pinfunction "2_2") (pintype "passive"))
      (node (ref "U300") (pin "8") (pinfunction "RG_8") (pintype "passive"))
    )
    (net (code "33") (name "Net-(R310-Pad2)") (class "Default")
      (node (ref "R310") (pin "2") (pinfunction "2_2") (pintype "passive"))
      (node (ref "U300") (pin "1") (pinfunction "RG_1") (pintype "passive"))
    )
    (net (code "34") (name "Net-(R313-Pad1)") (class "Default")
      (node (ref "R313") (pin "1") (pinfunction "1_1") (pintype "passive"))
      (node (ref "R314") (pin "1") (pinfunction "1_1") (pintype "passive"))
      (node (ref "R318") (pin "2") (pinfunction "2_2") (pintype "passive"))
      (node (ref "R319") (pin "2") (pinfunction "2_2") (pintype "passive"))
    )
    (net (code "35") (name "Net-(R321-Pad2)") (class "Default")
      (node (ref "R321") (pin "2") (pinfunction "2_2") (pintype "passive"))
      (node (ref "U302") (pin "8") (pinfunction "RG_8") (pintype "passive"))
    )
    (net (code "36") (name "Net-(R323-Pad2)") (class "Default")
      (node (ref "R323") (pin "2") (pinfunction "2_2") (pintype "passive"))
      (node (ref "U302") (pin "1") (pinfunction "RG_1") (pintype "passive"))
    )
    (net (code "37") (name "Net-(U300-IN+)") (class "Default")
      (node (ref "C300") (pin "1") (pinfunction "1_1") (pintype "passive"))
      (node (ref "R301") (pin "2") (pinfunction "2_2") (pintype "passive"))
      (node (ref "U300") (pin "3") (pinfunction "IN+_3") (pintype "passive"))
    )
    (net (code "38") (name "Net-(U300-IN-)") (class "Default")
      (node (ref "C306") (pin "1") (pinfunction "1_1") (pintype "passive"))
      (node (ref "R306") (pin "1") (pinfunction "1_1") (pintype "passive"))
      (node (ref "U300") (pin "2") (pinfunction "IN-_2") (pintype "passive"))
    )
    (net (code "39") (name "Net-(U300-OUT)") (class "Default")
      (node (ref "R302") (pin "1") (pinfunction "1_1") (pintype "passive"))
      (node (ref "R304") (pin "2") (pinfunction "2_2") (pintype "passive"))
      (node (ref "TP300") (pin "1") (pinfunction "1_1") (pintype "passive"))
      (node (ref "U300") (pin "6") (pinfunction "OUT_6") (pintype "passive"))
    )
    (net (code "40") (name "Net-(U300-VREF)") (class "Default")
      (node (ref "C307") (pin "1") (pinfunction "1_1") (pintype "passive"))
      (node (ref "R307") (pin "2") (pinfunction "2_2") (pintype "passive"))
      (node (ref "U300") (pin "5") (pinfunction "VREF_5") (pintype "passive"))
      (node (ref "U301") (pin "1") (pinfunction "1OUT_1") (pintype "passive"))
    )
    (net (code "41") (name "Net-(U301A-1IN-)") (class "Default")
      (node (ref "C308") (pin "2") (pinfunction "2_2") (pintype "passive"))
      (node (ref "R304") (pin "1") (pinfunction "1_1") (pintype "passive"))
      (node (ref "U301") (pin "2") (pinfunction "1IN-_2") (pintype "passive"))
    )
    (net (code "42") (name "Net-(U301B-2IN+)") (class "Default")
      (node (ref "C305") (pin "2") (pinfunction "2_2") (pintype "passive"))
      (node (ref "R303") (pin "2") (pinfunction "2_2") (pintype "passive"))
      (node (ref "U301") (pin "5") (pinfunction "2IN+_5") (pintype "passive"))
    )
    (net (code "43") (name "Net-(U301B-2IN-)") (class "Default")
      (node (ref "R311") (pin "1") (pinfunction "1_1") (pintype "passive"))
      (node (ref "R312") (pin "2") (pinfunction "2_2") (pintype "passive"))
      (node (ref "U301") (pin "6") (pinfunction "2IN-_6") (pintype "passive"))
    )
    (net (code "44") (name "Net-(U302-IN+)") (class "Default")
      (node (ref "C309") (pin "1") (pinfunction "1_1") (pintype "passive"))
      (node (ref "R314") (pin "2") (pinfunction "2_2") (pintype "passive"))
      (node (ref "U302") (pin "3") (pinfunction "IN+_3") (pintype "passive"))
    )
    (net (code "45") (name "Net-(U302-IN-)") (class "Default")
      (node (ref "C315") (pin "1") (pinfunction "1_1") (pintype "passive"))
      (node (ref "R319") (pin "1") (pinfunction "1_1") (pintype "passive"))
      (node (ref "U302") (pin "2") (pinfunction "IN-_2") (pintype "passive"))
    )
    (net (code "46") (name "Net-(U302-OUT)") (class "Default")
      (node (ref "R315") (pin "1") (pinfunction "1_1") (pintype "passive"))
      (node (ref "R317") (pin "2") (pinfunction "2_2") (pintype "passive"))
      (node (ref "TP302") (pin "1") (pinfunction "1_1") (pintype "passive"))
      (node (ref "U302") (pin "6") (pinfunction "OUT_6") (pintype "passive"))
    )
    (net (code "47") (name "Net-(U302-VREF)") (class "Default")
      (node (ref "C316") (pin "1") (pinfunction "1_1") (pintype "passive"))
      (node (ref "R320") (pin "2") (pinfunction "2_2") (pintype "passive"))
      (node (ref "U302") (pin "5") (pinfunction "VREF_5") (pintype "passive"))
      (node (ref "U303") (pin "1") (pinfunction "1OUT_1") (pintype "passive"))
    )
    (net (code "48") (name "Net-(U303A-1IN-)") (class "Default")
      (node (ref "C317") (pin "2") (pinfunction "2_2") (pintype "passive"))
      (node (ref "R317") (pin "1") (pinfunction "1_1") (pintype "passive"))
      (node (ref "U303") (pin "2") (pinfunction "1IN-_2") (pintype "passive"))
    )
    (net (code "49") (name "Net-(U303B-2IN+)") (class "Default")
      (node (ref "C314") (pin "2") (pinfunction "2_2") (pintype "passive"))
      (node (ref "R316") (pin "2") (pinfunction "2_2") (pintype "passive"))
      (node (ref "U303") (pin "5") (pinfunction "2IN+_5") (pintype "passive"))
    )
    (net (code "50") (name "Net-(U303B-2IN-)") (class "Default")
      (node (ref "R324") (pin "1") (pinfunction "1_1") (pintype "passive"))
      (node (ref "R325") (pin "2") (pinfunction "2_2") (pintype "passive"))
      (node (ref "U303") (pin "6") (pinfunction "2IN-_6") (pintype "passive"))
    )
    (net (code "51") (name "Net-(U304A-1IN-)") (class "Default")
      (node (ref "R327") (pin "2") (pinfunction "2_2") (pintype "passive"))
      (node (ref "U304") (pin "1") (pinfunction "1OUT_1") (pintype "passive"))
      (node (ref "U304") (pin "2") (pinfunction "1IN-_2") (pintype "passive"))
    )
    (net (code "52") (name "Net-(U304B-2IN-)") (class "Default")
      (node (ref "R329") (pin "2") (pinfunction "2_2") (pintype "passive"))
      (node (ref "U304") (pin "6") (pinfunction "2IN-_6") (pintype "passive"))
      (node (ref "U304") (pin "7") (pinfunction "2OUT_7") (pintype "passive"))
    )
  )
)
